# LEDDriverBoardV1_2.net
KiCad netlist of a schematic drawn in EAGLE
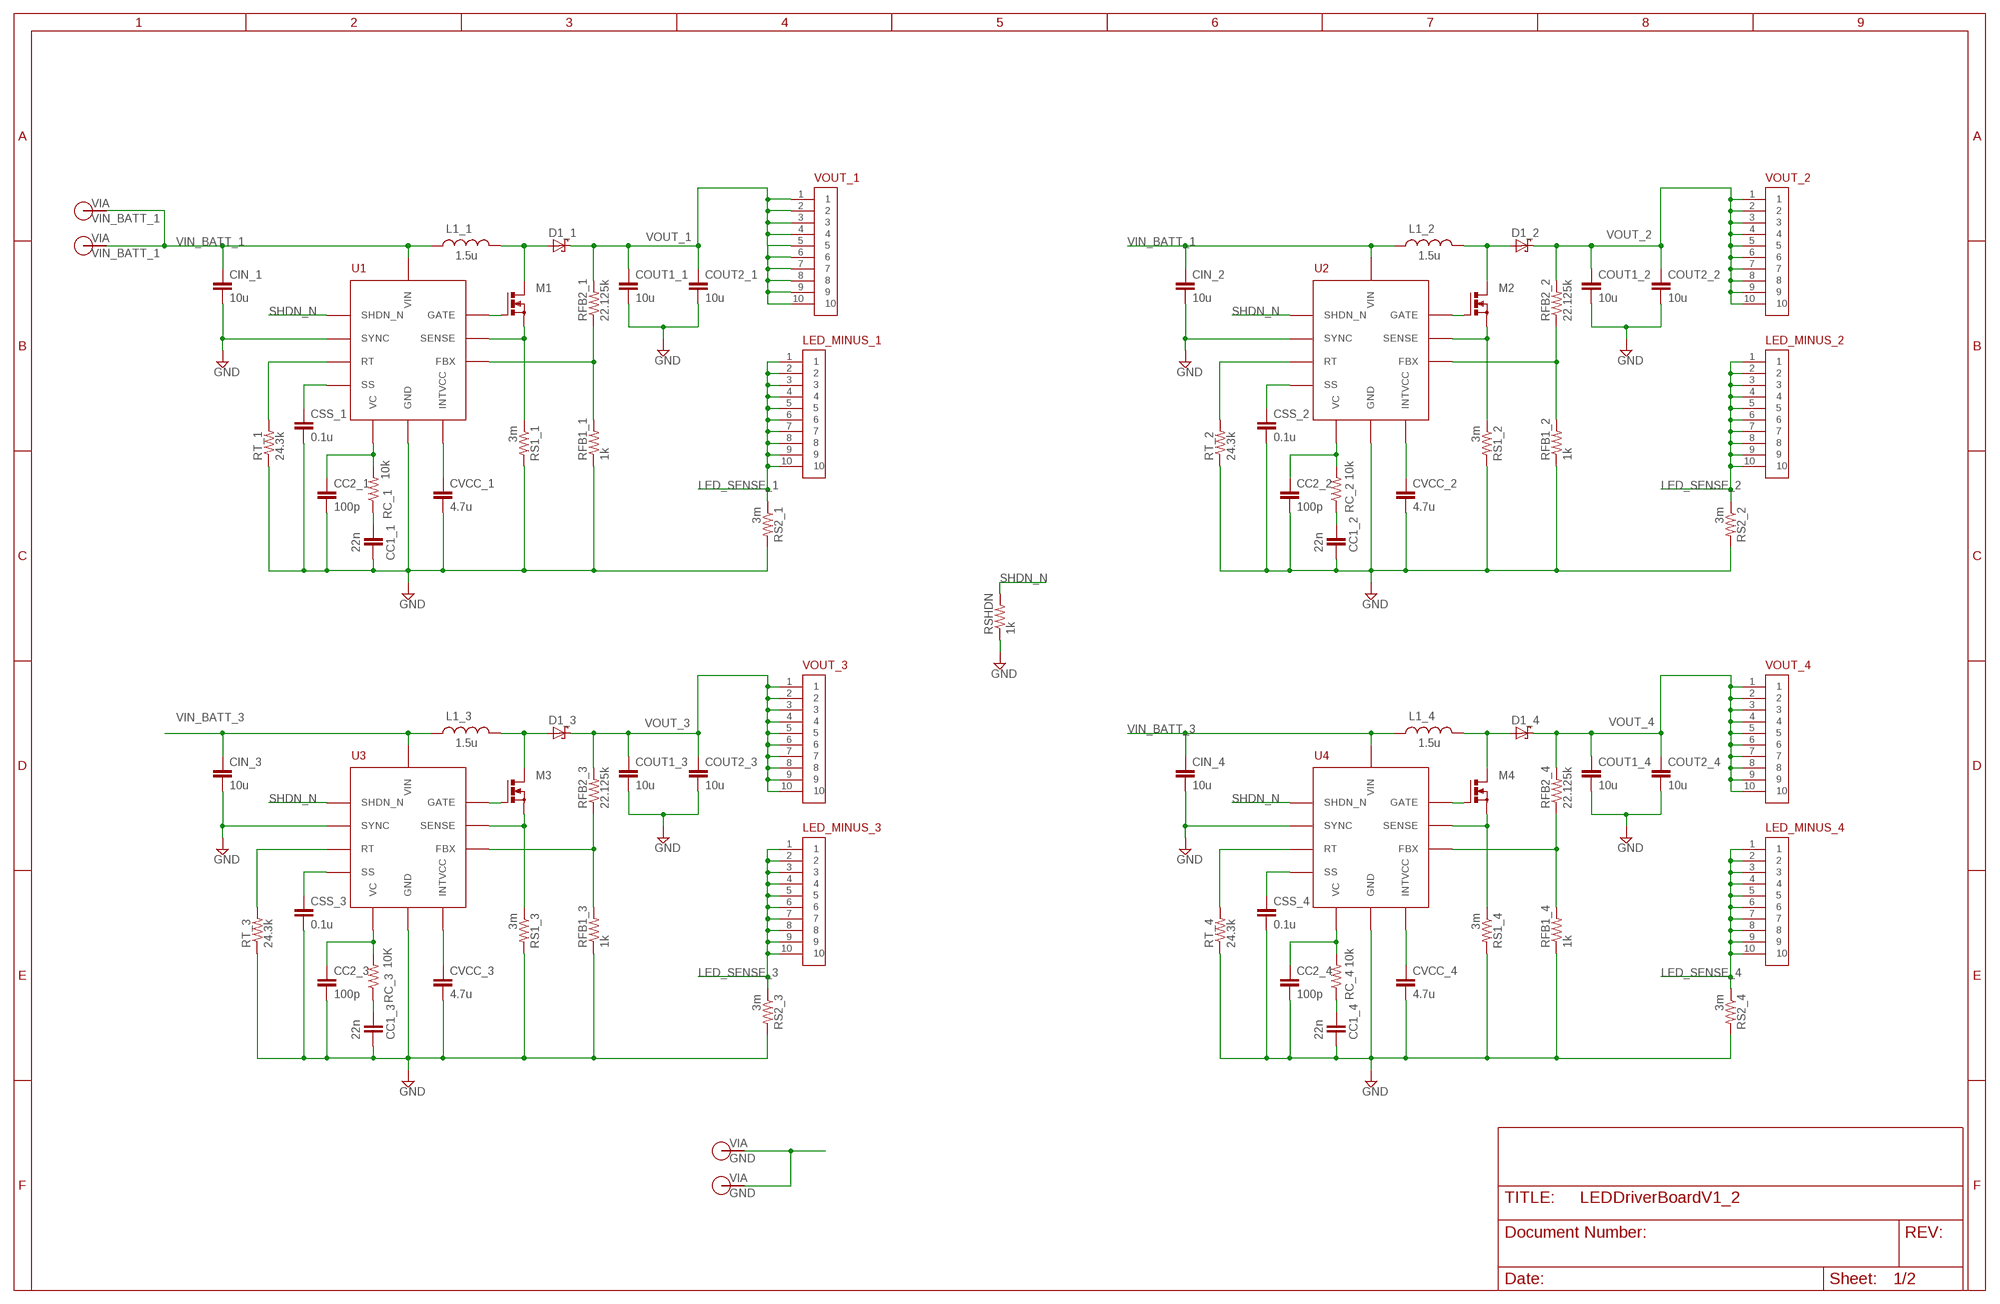
[diagram p0: schematic, sheet 1]
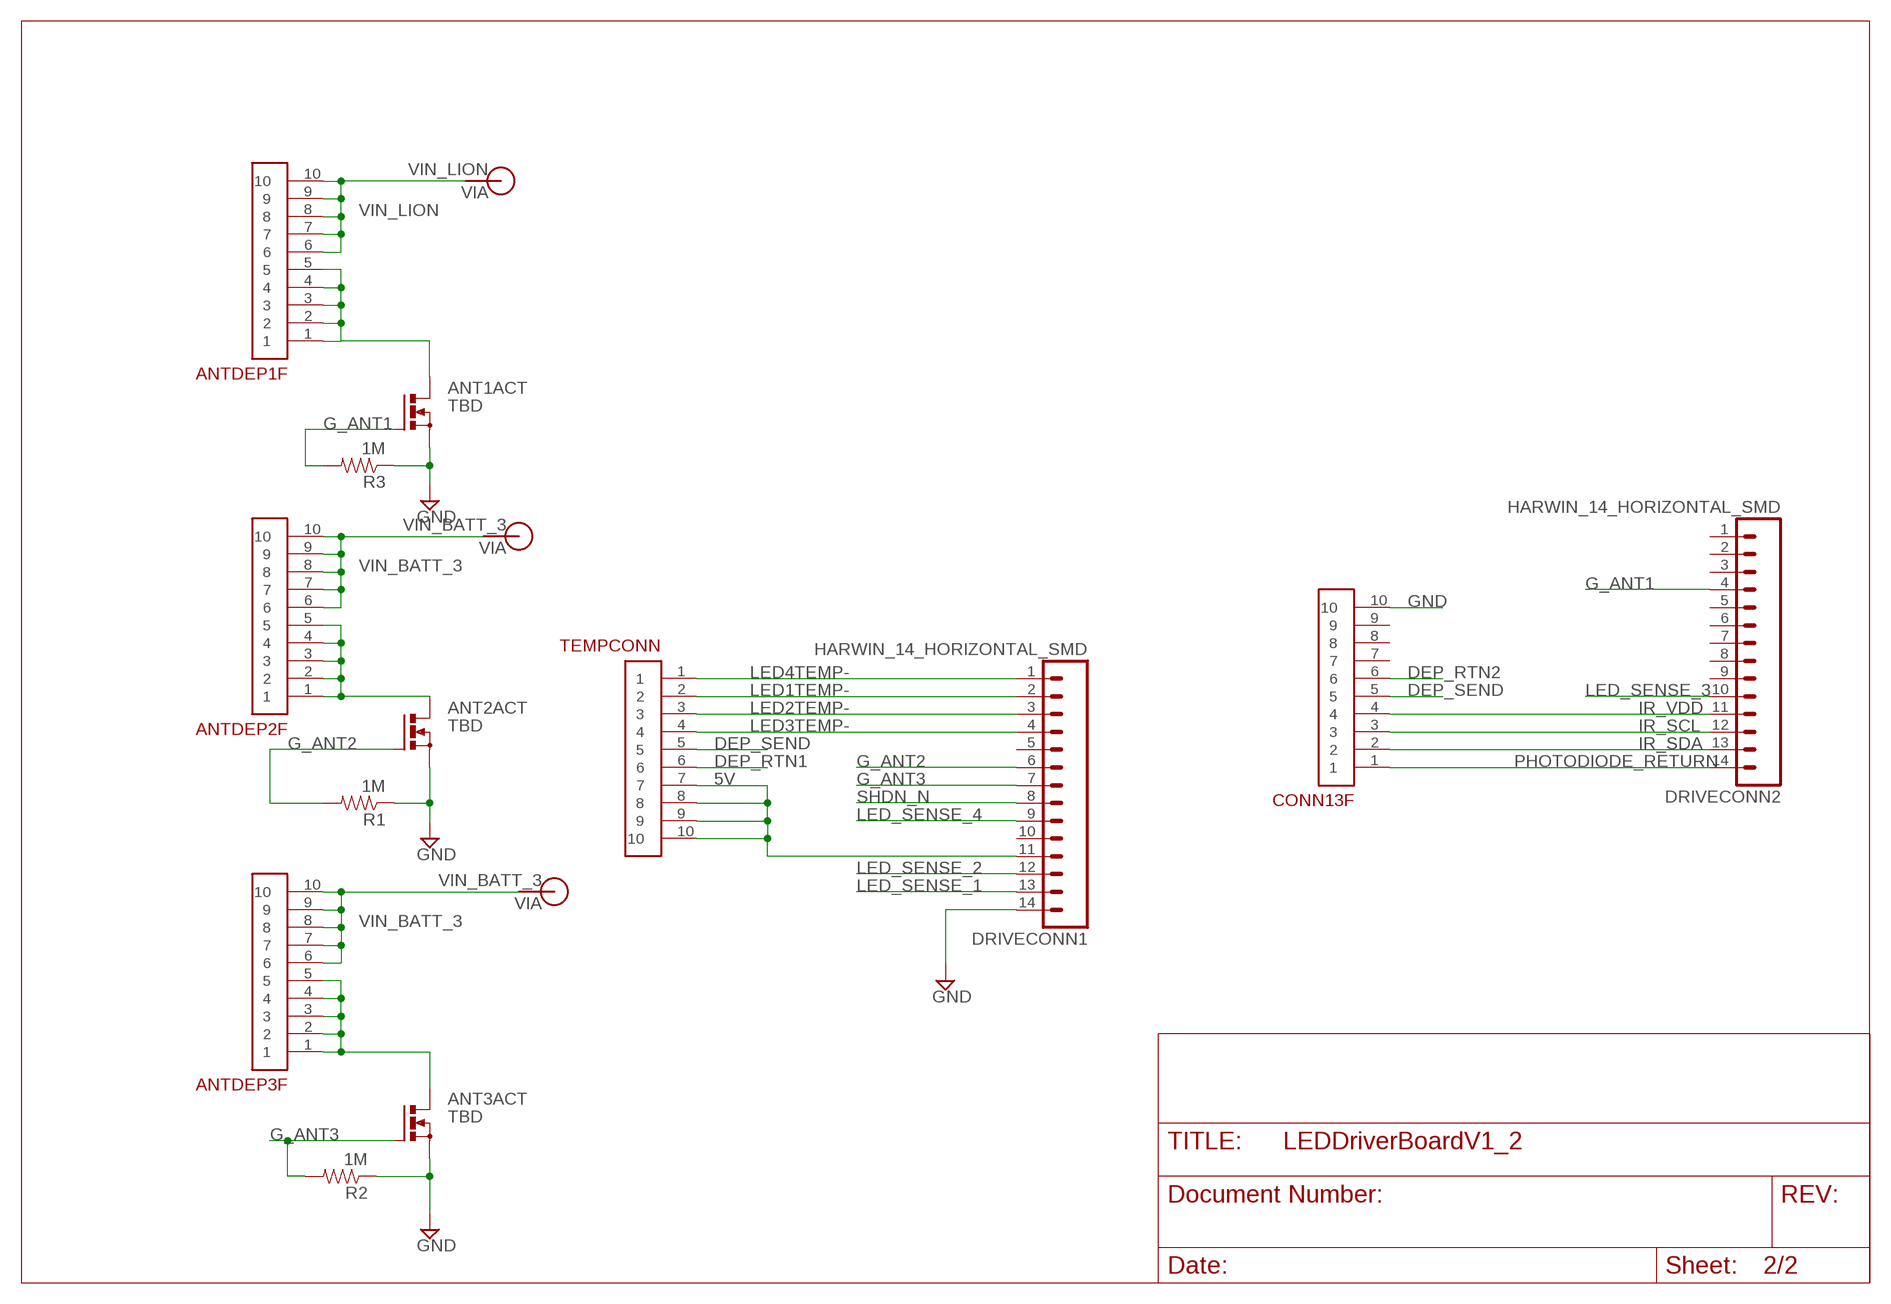
[diagram p1: schematic, sheet 2]

(export (version "E")
  (design (tool "Eeschema 10.0.6"))
  (components
    (comp (ref "CC1_1")
      (value "22n")
      (footprint "eagle-import:C0603")
      (libsource (lib "eagle-import") (part "C-EUC0603"))
    )
    (comp (ref "CC1_2")
      (value "22n")
      (footprint "eagle-import:C0603")
      (libsource (lib "eagle-import") (part "C-EUC0603"))
    )
    (comp (ref "CC1_3")
      (value "22n")
      (footprint "eagle-import:C0603")
      (libsource (lib "eagle-import") (part "C-EUC0603"))
    )
    (comp (ref "CC1_4")
      (value "22n")
      (footprint "eagle-import:C0603")
      (libsource (lib "eagle-import") (part "C-EUC0603"))
    )
    (comp (ref "CC2_1")
      (value "100p")
      (footprint "eagle-import:C0603")
      (libsource (lib "eagle-import") (part "C-EUC0603"))
    )
    (comp (ref "CC2_2")
      (value "100p")
      (footprint "eagle-import:C0603")
      (libsource (lib "eagle-import") (part "C-EUC0603"))
    )
    (comp (ref "CC2_3")
      (value "100p")
      (footprint "eagle-import:C0603")
      (libsource (lib "eagle-import") (part "C-EUC0603"))
    )
    (comp (ref "CC2_4")
      (value "100p")
      (footprint "eagle-import:C0603")
      (libsource (lib "eagle-import") (part "C-EUC0603"))
    )
    (comp (ref "CIN_1")
      (value "10u")
      (footprint "eagle-import:C1210")
      (libsource (lib "eagle-import") (part "C-EUC1210"))
    )
    (comp (ref "CIN_2")
      (value "10u")
      (footprint "eagle-import:C1210")
      (libsource (lib "eagle-import") (part "C-EUC1210"))
    )
    (comp (ref "CIN_3")
      (value "10u")
      (footprint "eagle-import:C1210")
      (libsource (lib "eagle-import") (part "C-EUC1210"))
    )
    (comp (ref "CIN_4")
      (value "10u")
      (footprint "eagle-import:C1210")
      (libsource (lib "eagle-import") (part "C-EUC1210"))
    )
    (comp (ref "COUT1_1")
      (value "10u")
      (footprint "eagle-import:C1210")
      (libsource (lib "eagle-import") (part "C-EUC1210"))
    )
    (comp (ref "COUT1_2")
      (value "10u")
      (footprint "eagle-import:C1210")
      (libsource (lib "eagle-import") (part "C-EUC1210"))
    )
    (comp (ref "COUT1_3")
      (value "10u")
      (footprint "eagle-import:C1210")
      (libsource (lib "eagle-import") (part "C-EUC1210"))
    )
    (comp (ref "COUT1_4")
      (value "10u")
      (footprint "eagle-import:C1210")
      (libsource (lib "eagle-import") (part "C-EUC1210"))
    )
    (comp (ref "COUT2_1")
      (value "10u")
      (footprint "eagle-import:C1210")
      (libsource (lib "eagle-import") (part "C-EUC1210"))
    )
    (comp (ref "COUT2_2")
      (value "10u")
      (footprint "eagle-import:C1210")
      (libsource (lib "eagle-import") (part "C-EUC1210"))
    )
    (comp (ref "COUT2_3")
      (value "10u")
      (footprint "eagle-import:C1210")
      (libsource (lib "eagle-import") (part "C-EUC1210"))
    )
    (comp (ref "COUT2_4")
      (value "10u")
      (footprint "eagle-import:C1210")
      (libsource (lib "eagle-import") (part "C-EUC1210"))
    )
    (comp (ref "CSS_1")
      (value "0.1u")
      (footprint "eagle-import:C0603")
      (libsource (lib "eagle-import") (part "C-EUC0603"))
    )
    (comp (ref "CSS_2")
      (value "0.1u")
      (footprint "eagle-import:C0603")
      (libsource (lib "eagle-import") (part "C-EUC0603"))
    )
    (comp (ref "CSS_3")
      (value "0.1u")
      (footprint "eagle-import:C0603")
      (libsource (lib "eagle-import") (part "C-EUC0603"))
    )
    (comp (ref "CSS_4")
      (value "0.1u")
      (footprint "eagle-import:C0603")
      (libsource (lib "eagle-import") (part "C-EUC0603"))
    )
    (comp (ref "CVCC_1")
      (value "4.7u")
      (footprint "eagle-import:C0603")
      (libsource (lib "eagle-import") (part "C-EUC0603"))
    )
    (comp (ref "CVCC_2")
      (value "4.7u")
      (footprint "eagle-import:C0603")
      (libsource (lib "eagle-import") (part "C-EUC0603"))
    )
    (comp (ref "CVCC_3")
      (value "4.7u")
      (footprint "eagle-import:C0603")
      (libsource (lib "eagle-import") (part "C-EUC0603"))
    )
    (comp (ref "CVCC_4")
      (value "4.7u")
      (footprint "eagle-import:C0603")
      (libsource (lib "eagle-import") (part "C-EUC0603"))
    )
    (comp (ref "D1_1")
      (value "CDBZ5T30100-HF")
      (footprint "eagle-import:SMC(Z5-T)")
      (libsource (lib "eagle-import") (part "CDBZ5T30100-HF"))
    )
    (comp (ref "D1_2")
      (value "CDBZ5T30100-HF")
      (footprint "eagle-import:SMC(Z5-T)")
      (libsource (lib "eagle-import") (part "CDBZ5T30100-HF"))
    )
    (comp (ref "D1_3")
      (value "CDBZ5T30100-HF")
      (footprint "eagle-import:SMC(Z5-T)")
      (libsource (lib "eagle-import") (part "CDBZ5T30100-HF"))
    )
    (comp (ref "D1_4")
      (value "CDBZ5T30100-HF")
      (footprint "eagle-import:SMC(Z5-T)")
      (libsource (lib "eagle-import") (part "CDBZ5T30100-HF"))
    )
    (comp (ref "L1_1")
      (value "1.5u")
      (footprint "eagle-import:SRP1245A")
      (libsource (lib "eagle-import") (part "SRP1245A-1R5M"))
    )
    (comp (ref "L1_2")
      (value "1.5u")
      (footprint "eagle-import:SRP1245A")
      (libsource (lib "eagle-import") (part "SRP1245A-1R5M"))
    )
    (comp (ref "L1_3")
      (value "1.5u")
      (footprint "eagle-import:SRP1245A")
      (libsource (lib "eagle-import") (part "SRP1245A-1R5M"))
    )
    (comp (ref "L1_4")
      (value "1.5u")
      (footprint "eagle-import:SRP1245A")
      (libsource (lib "eagle-import") (part "SRP1245A-1R5M"))
    )
    (comp (ref "LED_MINUS_1")
      (value "M50-3120545")
      (footprint "eagle-import:10PINFEMALE")
      (libsource (lib "eagle-import") (part "M50-3120545"))
    )
    (comp (ref "LED_MINUS_2")
      (value "M50-3120545")
      (footprint "eagle-import:10PINFEMALE")
      (libsource (lib "eagle-import") (part "M50-3120545"))
    )
    (comp (ref "LED_MINUS_3")
      (value "M50-3120545")
      (footprint "eagle-import:10PINFEMALE")
      (libsource (lib "eagle-import") (part "M50-3120545"))
    )
    (comp (ref "LED_MINUS_4")
      (value "M50-3120545")
      (footprint "eagle-import:10PINFEMALE")
      (libsource (lib "eagle-import") (part "M50-3120545"))
    )
    (comp (ref "M1")
      (value "STL110N10F7")
      (footprint "eagle-import:POWERFLAT")
      (libsource (lib "eagle-import") (part "STL110N10F7"))
    )
    (comp (ref "M2")
      (value "STL110N10F7")
      (footprint "eagle-import:POWERFLAT")
      (libsource (lib "eagle-import") (part "STL110N10F7"))
    )
    (comp (ref "M3")
      (value "STL110N10F7")
      (footprint "eagle-import:POWERFLAT")
      (libsource (lib "eagle-import") (part "STL110N10F7"))
    )
    (comp (ref "M4")
      (value "STL110N10F7")
      (footprint "eagle-import:POWERFLAT")
      (libsource (lib "eagle-import") (part "STL110N10F7"))
    )
    (comp (ref "RC_1")
      (value "10k")
      (footprint "eagle-import:R0603")
      (libsource (lib "eagle-import") (part "R-US_R0603"))
    )
    (comp (ref "RC_2")
      (value "10k")
      (footprint "eagle-import:R0603")
      (libsource (lib "eagle-import") (part "R-US_R0603"))
    )
    (comp (ref "RC_3")
      (value "10K")
      (footprint "eagle-import:R0603")
      (libsource (lib "eagle-import") (part "R-US_R0603"))
    )
    (comp (ref "RC_4")
      (value "10k")
      (footprint "eagle-import:R0603")
      (libsource (lib "eagle-import") (part "R-US_R0603"))
    )
    (comp (ref "RFB1_1")
      (value "1k")
      (footprint "eagle-import:R0603")
      (libsource (lib "eagle-import") (part "R-US_R0603"))
    )
    (comp (ref "RFB1_2")
      (value "1k")
      (footprint "eagle-import:R0603")
      (libsource (lib "eagle-import") (part "R-US_R0603"))
    )
    (comp (ref "RFB1_3")
      (value "1k")
      (footprint "eagle-import:R0603")
      (libsource (lib "eagle-import") (part "R-US_R0603"))
    )
    (comp (ref "RFB1_4")
      (value "1k")
      (footprint "eagle-import:R0603")
      (libsource (lib "eagle-import") (part "R-US_R0603"))
    )
    (comp (ref "RFB2_1")
      (value "22.125k")
      (footprint "eagle-import:R0603")
      (libsource (lib "eagle-import") (part "R-US_R0603"))
    )
    (comp (ref "RFB2_2")
      (value "22.125k")
      (footprint "eagle-import:R0603")
      (libsource (lib "eagle-import") (part "R-US_R0603"))
    )
    (comp (ref "RFB2_3")
      (value "22.125k")
      (footprint "eagle-import:R0603")
      (libsource (lib "eagle-import") (part "R-US_R0603"))
    )
    (comp (ref "RFB2_4")
      (value "22.125k")
      (footprint "eagle-import:R0603")
      (libsource (lib "eagle-import") (part "R-US_R0603"))
    )
    (comp (ref "RS1_1")
      (value "3m")
      (footprint "eagle-import:ERJMS4S")
      (libsource (lib "eagle-import") (part "ERJMS4S"))
    )
    (comp (ref "RS1_2")
      (value "3m")
      (footprint "eagle-import:ERJMS4S")
      (libsource (lib "eagle-import") (part "ERJMS4S"))
    )
    (comp (ref "RS1_3")
      (value "3m")
      (footprint "eagle-import:ERJMS4S")
      (libsource (lib "eagle-import") (part "ERJMS4S"))
    )
    (comp (ref "RS1_4")
      (value "3m")
      (footprint "eagle-import:ERJMS4S")
      (libsource (lib "eagle-import") (part "ERJMS4S"))
    )
    (comp (ref "RS2_1")
      (value "3m")
      (footprint "eagle-import:ERJMS4S")
      (libsource (lib "eagle-import") (part "ERJMS4S"))
    )
    (comp (ref "RS2_2")
      (value "3m")
      (footprint "eagle-import:ERJMS4S")
      (libsource (lib "eagle-import") (part "ERJMS4S"))
    )
    (comp (ref "RS2_3")
      (value "3m")
      (footprint "eagle-import:ERJMS4S")
      (libsource (lib "eagle-import") (part "ERJMS4S"))
    )
    (comp (ref "RS2_4")
      (value "3m")
      (footprint "eagle-import:ERJMS4S")
      (libsource (lib "eagle-import") (part "ERJMS4S"))
    )
    (comp (ref "RSHDN")
      (value "1k")
      (footprint "eagle-import:R0603")
      (libsource (lib "eagle-import") (part "R-US_R0603"))
    )
    (comp (ref "RT_1")
      (value "24.3k")
      (footprint "eagle-import:R0603")
      (libsource (lib "eagle-import") (part "R-US_R0603"))
    )
    (comp (ref "RT_2")
      (value "24.3k")
      (footprint "eagle-import:R0603")
      (libsource (lib "eagle-import") (part "R-US_R0603"))
    )
    (comp (ref "RT_3")
      (value "24.3k")
      (footprint "eagle-import:R0603")
      (libsource (lib "eagle-import") (part "R-US_R0603"))
    )
    (comp (ref "RT_4")
      (value "24.3k")
      (footprint "eagle-import:R0603")
      (libsource (lib "eagle-import") (part "R-US_R0603"))
    )
    (comp (ref "U1")
      (value "LT3757")
      (footprint "eagle-import:MSOP10")
      (libsource (lib "eagle-import") (part "LT3757"))
    )
    (comp (ref "U2")
      (value "LT3757")
      (footprint "eagle-import:MSOP10")
      (libsource (lib "eagle-import") (part "LT3757"))
    )
    (comp (ref "U3")
      (value "LT3757")
      (footprint "eagle-import:MSOP10")
      (libsource (lib "eagle-import") (part "LT3757"))
    )
    (comp (ref "U4")
      (value "LT3757")
      (footprint "eagle-import:MSOP10")
      (libsource (lib "eagle-import") (part "LT3757"))
    )
    (comp (ref "V1")
      (value "GND")
      (footprint "eagle-import:VIA-120MIL")
      (libsource (lib "eagle-import") (part "VIA-120MIL"))
    )
    (comp (ref "V5")
      (value "GND")
      (footprint "eagle-import:VIA-120MIL")
      (libsource (lib "eagle-import") (part "VIA-120MIL"))
    )
    (comp (ref "V6")
      (value "VIN_BATT_1")
      (footprint "eagle-import:VIA-120MIL")
      (libsource (lib "eagle-import") (part "VIA-120MIL"))
    )
    (comp (ref "V7")
      (value "VIN_BATT_1")
      (footprint "eagle-import:VIA-120MIL")
      (libsource (lib "eagle-import") (part "VIA-120MIL"))
    )
    (comp (ref "VOUT_1")
      (value "M50-3120545")
      (footprint "eagle-import:10PINFEMALE")
      (libsource (lib "eagle-import") (part "M50-3120545"))
    )
    (comp (ref "VOUT_2")
      (value "M50-3120545")
      (footprint "eagle-import:10PINFEMALE")
      (libsource (lib "eagle-import") (part "M50-3120545"))
    )
    (comp (ref "VOUT_3")
      (value "M50-3120545")
      (footprint "eagle-import:10PINFEMALE")
      (libsource (lib "eagle-import") (part "M50-3120545"))
    )
    (comp (ref "VOUT_4")
      (value "M50-3120545")
      (footprint "eagle-import:10PINFEMALE")
      (libsource (lib "eagle-import") (part "M50-3120545"))
    )
    (comp (ref "ANT1ACT")
      (value "TBD")
      (footprint "eagle-import:DFN3.3X3.3")
      (libsource (lib "eagle-import") (part "AON7292"))
    )
    (comp (ref "ANT2ACT")
      (value "TBD")
      (footprint "eagle-import:DFN3.3X3.3")
      (libsource (lib "eagle-import") (part "AON7292"))
    )
    (comp (ref "ANT3ACT")
      (value "TBD")
      (footprint "eagle-import:DFN3.3X3.3")
      (libsource (lib "eagle-import") (part "AON7292"))
    )
    (comp (ref "ANTDEP1F")
      (value "M50-3120545")
      (footprint "eagle-import:10PINFEMALE")
      (libsource (lib "eagle-import") (part "M50-3120545"))
    )
    (comp (ref "ANTDEP2F")
      (value "M50-3120545")
      (footprint "eagle-import:10PINFEMALE")
      (libsource (lib "eagle-import") (part "M50-3120545"))
    )
    (comp (ref "ANTDEP3F")
      (value "M50-3120545")
      (footprint "eagle-import:10PINFEMALE")
      (libsource (lib "eagle-import") (part "M50-3120545"))
    )
    (comp (ref "CONN13F")
      (value "M50-3120545")
      (footprint "eagle-import:10PINFEMALE")
      (libsource (lib "eagle-import") (part "M50-3120545"))
    )
    (comp (ref "DRIVECONN1")
      (value "HARWIN_14_HORIZONTAL_SMD")
      (footprint "eagle-import:14PINMALE_SMD")
      (libsource (lib "eagle-import") (part "M80-5321442"))
    )
    (comp (ref "DRIVECONN2")
      (value "HARWIN_14_HORIZONTAL_SMD")
      (footprint "eagle-import:14PINMALE_SMD")
      (libsource (lib "eagle-import") (part "M80-5321442"))
    )
    (comp (ref "R1")
      (value "1M")
      (footprint "eagle-import:0805")
      (libsource (lib "eagle-import") (part "RESISTOR"))
    )
    (comp (ref "R2")
      (value "1M")
      (footprint "eagle-import:0805")
      (libsource (lib "eagle-import") (part "RESISTOR"))
    )
    (comp (ref "R3")
      (value "1M")
      (footprint "eagle-import:0805")
      (libsource (lib "eagle-import") (part "RESISTOR"))
    )
    (comp (ref "TEMPCONN")
      (value "M50-3120545")
      (footprint "eagle-import:10PINFEMALE")
      (libsource (lib "eagle-import") (part "M50-3120545"))
    )
    (comp (ref "V2")
      (value "VIN_BATT_3")
      (footprint "eagle-import:VIA-120MIL")
      (libsource (lib "eagle-import") (part "VIA-120MIL"))
    )
    (comp (ref "V3")
      (value "VIN_BATT_3")
      (footprint "eagle-import:VIA-120MIL")
      (libsource (lib "eagle-import") (part "VIA-120MIL"))
    )
    (comp (ref "V4")
      (value "VIN_LION")
      (footprint "eagle-import:VIA-120MIL")
      (libsource (lib "eagle-import") (part "VIA-120MIL"))
    )
  )
  (nets
    (net (code "1") (name "5V") (class "Default")
      (node (ref "DRIVECONN1") (pin "11") (pinfunction "11_11") (pintype "passive"))
      (node (ref "TEMPCONN") (pin "10") (pinfunction "10_10") (pintype "bidirectional"))
      (node (ref "TEMPCONN") (pin "7") (pinfunction "7_7") (pintype "bidirectional"))
      (node (ref "TEMPCONN") (pin "8") (pinfunction "8_8") (pintype "bidirectional"))
      (node (ref "TEMPCONN") (pin "9") (pinfunction "9_9") (pintype "bidirectional"))
    )
    (net (code "2") (name "DEP_RTN1") (class "Default")
      (node (ref "TEMPCONN") (pin "6") (pinfunction "6_6") (pintype "bidirectional"))
    )
    (net (code "3") (name "DEP_RTN2") (class "Default")
      (node (ref "CONN13F") (pin "6") (pinfunction "6_6") (pintype "bidirectional"))
    )
    (net (code "4") (name "DEP_SEND") (class "Default")
      (node (ref "CONN13F") (pin "5") (pinfunction "5_5") (pintype "bidirectional"))
      (node (ref "TEMPCONN") (pin "5") (pinfunction "5_5") (pintype "bidirectional"))
    )
    (net (code "5") (name "GND") (class "Default")
      (node (ref "ANT1ACT") (pin "S1") (pinfunction "S_S1") (pintype "passive"))
      (node (ref "ANT1ACT") (pin "S2") (pinfunction "S_S2") (pintype "passive"))
      (node (ref "ANT1ACT") (pin "S3") (pinfunction "S_S3") (pintype "passive"))
      (node (ref "ANT2ACT") (pin "S1") (pinfunction "S_S1") (pintype "passive"))
      (node (ref "ANT2ACT") (pin "S2") (pinfunction "S_S2") (pintype "passive"))
      (node (ref "ANT2ACT") (pin "S3") (pinfunction "S_S3") (pintype "passive"))
      (node (ref "ANT3ACT") (pin "S1") (pinfunction "S_S1") (pintype "passive"))
      (node (ref "ANT3ACT") (pin "S2") (pinfunction "S_S2") (pintype "passive"))
      (node (ref "ANT3ACT") (pin "S3") (pinfunction "S_S3") (pintype "passive"))
      (node (ref "CC1_1") (pin "2") (pinfunction "2_2") (pintype "passive"))
      (node (ref "CC1_2") (pin "2") (pinfunction "2_2") (pintype "passive"))
      (node (ref "CC1_3") (pin "2") (pinfunction "2_2") (pintype "passive"))
      (node (ref "CC1_4") (pin "2") (pinfunction "2_2") (pintype "passive"))
      (node (ref "CC2_1") (pin "2") (pinfunction "2_2") (pintype "passive"))
      (node (ref "CC2_2") (pin "2") (pinfunction "2_2") (pintype "passive"))
      (node (ref "CC2_3") (pin "2") (pinfunction "2_2") (pintype "passive"))
      (node (ref "CC2_4") (pin "2") (pinfunction "2_2") (pintype "passive"))
      (node (ref "CIN_1") (pin "2") (pinfunction "2_2") (pintype "passive"))
      (node (ref "CIN_2") (pin "2") (pinfunction "2_2") (pintype "passive"))
      (node (ref "CIN_3") (pin "2") (pinfunction "2_2") (pintype "passive"))
      (node (ref "CIN_4") (pin "2") (pinfunction "2_2") (pintype "passive"))
      (node (ref "CONN13F") (pin "10") (pinfunction "10_10") (pintype "bidirectional"))
      (node (ref "COUT1_1") (pin "2") (pinfunction "2_2") (pintype "passive"))
      (node (ref "COUT1_2") (pin "2") (pinfunction "2_2") (pintype "passive"))
      (node (ref "COUT1_3") (pin "2") (pinfunction "2_2") (pintype "passive"))
      (node (ref "COUT1_4") (pin "2") (pinfunction "2_2") (pintype "passive"))
      (node (ref "COUT2_1") (pin "2") (pinfunction "2_2") (pintype "passive"))
      (node (ref "COUT2_2") (pin "2") (pinfunction "2_2") (pintype "passive"))
      (node (ref "COUT2_3") (pin "2") (pinfunction "2_2") (pintype "passive"))
      (node (ref "COUT2_4") (pin "2") (pinfunction "2_2") (pintype "passive"))
      (node (ref "CSS_1") (pin "2") (pinfunction "2_2") (pintype "passive"))
      (node (ref "CSS_2") (pin "2") (pinfunction "2_2") (pintype "passive"))
      (node (ref "CSS_3") (pin "2") (pinfunction "2_2") (pintype "passive"))
      (node (ref "CSS_4") (pin "2") (pinfunction "2_2") (pintype "passive"))
      (node (ref "CVCC_1") (pin "2") (pinfunction "2_2") (pintype "passive"))
      (node (ref "CVCC_2") (pin "2") (pinfunction "2_2") (pintype "passive"))
      (node (ref "CVCC_3") (pin "2") (pinfunction "2_2") (pintype "passive"))
      (node (ref "CVCC_4") (pin "2") (pinfunction "2_2") (pintype "passive"))
      (node (ref "DRIVECONN1") (pin "14") (pinfunction "14_14") (pintype "passive"))
      (node (ref "R1") (pin "1") (pinfunction "1_1") (pintype "passive"))
      (node (ref "R2") (pin "1") (pinfunction "1_1") (pintype "passive"))
      (node (ref "R3") (pin "1") (pinfunction "1_1") (pintype "passive"))
      (node (ref "RFB1_1") (pin "1") (pinfunction "1_1") (pintype "passive"))
      (node (ref "RFB1_2") (pin "1") (pinfunction "1_1") (pintype "passive"))
      (node (ref "RFB1_3") (pin "1") (pinfunction "1_1") (pintype "passive"))
      (node (ref "RFB1_4") (pin "1") (pinfunction "1_1") (pintype "passive"))
      (node (ref "RS1_1") (pin "B") (pinfunction "2_B") (pintype "passive"))
      (node (ref "RS1_2") (pin "B") (pinfunction "2_B") (pintype "passive"))
      (node (ref "RS1_3") (pin "B") (pinfunction "2_B") (pintype "passive"))
      (node (ref "RS1_4") (pin "B") (pinfunction "2_B") (pintype "passive"))
      (node (ref "RS2_1") (pin "B") (pinfunction "2_B") (pintype "passive"))
      (node (ref "RS2_2") (pin "B") (pinfunction "2_B") (pintype "passive"))
      (node (ref "RS2_3") (pin "B") (pinfunction "2_B") (pintype "passive"))
      (node (ref "RS2_4") (pin "B") (pinfunction "2_B") (pintype "passive"))
      (node (ref "RSHDN") (pin "1") (pinfunction "1_1") (pintype "passive"))
      (node (ref "RT_1") (pin "1") (pinfunction "1_1") (pintype "passive"))
      (node (ref "RT_2") (pin "1") (pinfunction "1_1") (pintype "passive"))
      (node (ref "RT_3") (pin "1") (pinfunction "1_1") (pintype "passive"))
      (node (ref "RT_4") (pin "1") (pinfunction "1_1") (pintype "passive"))
      (node (ref "U1") (pin "P$11") (pinfunction "GND_P$11") (pintype "bidirectional"))
      (node (ref "U1") (pin "P$5") (pinfunction "SYNC_P$5") (pintype "bidirectional"))
      (node (ref "U2") (pin "P$11") (pinfunction "GND_P$11") (pintype "bidirectional"))
      (node (ref "U2") (pin "P$5") (pinfunction "SYNC_P$5") (pintype "bidirectional"))
      (node (ref "U3") (pin "P$11") (pinfunction "GND_P$11") (pintype "bidirectional"))
      (node (ref "U3") (pin "P$5") (pinfunction "SYNC_P$5") (pintype "bidirectional"))
      (node (ref "U4") (pin "P$11") (pinfunction "GND_P$11") (pintype "bidirectional"))
      (node (ref "U4") (pin "P$5") (pinfunction "SYNC_P$5") (pintype "bidirectional"))
      (node (ref "V1") (pin "P$1") (pinfunction "P$1_P$1") (pintype "bidirectional"))
      (node (ref "V5") (pin "P$1") (pinfunction "P$1_P$1") (pintype "bidirectional"))
    )
    (net (code "6") (name "G_ANT1") (class "Default")
      (node (ref "ANT1ACT") (pin "G") (pinfunction "G_G") (pintype "passive"))
      (node (ref "DRIVECONN2") (pin "4") (pinfunction "4_4") (pintype "passive"))
      (node (ref "R3") (pin "2") (pinfunction "2_2") (pintype "passive"))
    )
    (net (code "7") (name "G_ANT2") (class "Default")
      (node (ref "ANT2ACT") (pin "G") (pinfunction "G_G") (pintype "passive"))
      (node (ref "DRIVECONN1") (pin "6") (pinfunction "6_6") (pintype "passive"))
      (node (ref "R1") (pin "2") (pinfunction "2_2") (pintype "passive"))
    )
    (net (code "8") (name "G_ANT3") (class "Default")
      (node (ref "ANT3ACT") (pin "G") (pinfunction "G_G") (pintype "passive"))
      (node (ref "DRIVECONN1") (pin "7") (pinfunction "7_7") (pintype "passive"))
      (node (ref "R2") (pin "2") (pinfunction "2_2") (pintype "passive"))
    )
    (net (code "9") (name "IR_SCL") (class "Default")
      (node (ref "CONN13F") (pin "3") (pinfunction "3_3") (pintype "bidirectional"))
      (node (ref "DRIVECONN2") (pin "12") (pinfunction "12_12") (pintype "passive"))
    )
    (net (code "10") (name "IR_SDA") (class "Default")
      (node (ref "CONN13F") (pin "2") (pinfunction "2_2") (pintype "bidirectional"))
      (node (ref "DRIVECONN2") (pin "13") (pinfunction "13_13") (pintype "passive"))
    )
    (net (code "11") (name "IR_VDD") (class "Default")
      (node (ref "CONN13F") (pin "4") (pinfunction "4_4") (pintype "bidirectional"))
      (node (ref "DRIVECONN2") (pin "11") (pinfunction "11_11") (pintype "passive"))
    )
    (net (code "12") (name "LED1TEMP-") (class "Default")
      (node (ref "DRIVECONN1") (pin "2") (pinfunction "2_2") (pintype "passive"))
      (node (ref "TEMPCONN") (pin "2") (pinfunction "2_2") (pintype "bidirectional"))
    )
    (net (code "13") (name "LED2TEMP-") (class "Default")
      (node (ref "DRIVECONN1") (pin "3") (pinfunction "3_3") (pintype "passive"))
      (node (ref "TEMPCONN") (pin "3") (pinfunction "3_3") (pintype "bidirectional"))
    )
    (net (code "14") (name "LED3TEMP-") (class "Default")
      (node (ref "DRIVECONN1") (pin "4") (pinfunction "4_4") (pintype "passive"))
      (node (ref "TEMPCONN") (pin "4") (pinfunction "4_4") (pintype "bidirectional"))
    )
    (net (code "15") (name "LED4TEMP-") (class "Default")
      (node (ref "DRIVECONN1") (pin "1") (pinfunction "1_1") (pintype "passive"))
      (node (ref "TEMPCONN") (pin "1") (pinfunction "1_1") (pintype "bidirectional"))
    )
    (net (code "16") (name "LED_SENSE_1") (class "Default")
      (node (ref "DRIVECONN1") (pin "13") (pinfunction "13_13") (pintype "passive"))
      (node (ref "LED_MINUS_1") (pin "1") (pinfunction "1_1") (pintype "bidirectional"))
      (node (ref "LED_MINUS_1") (pin "10") (pinfunction "10_10") (pintype "bidirectional"))
      (node (ref "LED_MINUS_1") (pin "2") (pinfunction "2_2") (pintype "bidirectional"))
      (node (ref "LED_MINUS_1") (pin "3") (pinfunction "3_3") (pintype "bidirectional"))
      (node (ref "LED_MINUS_1") (pin "4") (pinfunction "4_4") (pintype "bidirectional"))
      (node (ref "LED_MINUS_1") (pin "5") (pinfunction "5_5") (pintype "bidirectional"))
      (node (ref "LED_MINUS_1") (pin "6") (pinfunction "6_6") (pintype "bidirectional"))
      (node (ref "LED_MINUS_1") (pin "7") (pinfunction "7_7") (pintype "bidirectional"))
      (node (ref "LED_MINUS_1") (pin "8") (pinfunction "8_8") (pintype "bidirectional"))
      (node (ref "LED_MINUS_1") (pin "9") (pinfunction "9_9") (pintype "bidirectional"))
      (node (ref "RS2_1") (pin "A") (pinfunction "1_A") (pintype "passive"))
    )
    (net (code "17") (name "LED_SENSE_2") (class "Default")
      (node (ref "DRIVECONN1") (pin "12") (pinfunction "12_12") (pintype "passive"))
      (node (ref "LED_MINUS_2") (pin "1") (pinfunction "1_1") (pintype "bidirectional"))
      (node (ref "LED_MINUS_2") (pin "10") (pinfunction "10_10") (pintype "bidirectional"))
      (node (ref "LED_MINUS_2") (pin "2") (pinfunction "2_2") (pintype "bidirectional"))
      (node (ref "LED_MINUS_2") (pin "3") (pinfunction "3_3") (pintype "bidirectional"))
      (node (ref "LED_MINUS_2") (pin "4") (pinfunction "4_4") (pintype "bidirectional"))
      (node (ref "LED_MINUS_2") (pin "5") (pinfunction "5_5") (pintype "bidirectional"))
      (node (ref "LED_MINUS_2") (pin "6") (pinfunction "6_6") (pintype "bidirectional"))
      (node (ref "LED_MINUS_2") (pin "7") (pinfunction "7_7") (pintype "bidirectional"))
      (node (ref "LED_MINUS_2") (pin "8") (pinfunction "8_8") (pintype "bidirectional"))
      (node (ref "LED_MINUS_2") (pin "9") (pinfunction "9_9") (pintype "bidirectional"))
      (node (ref "RS2_2") (pin "A") (pinfunction "1_A") (pintype "passive"))
    )
    (net (code "18") (name "LED_SENSE_3") (class "Default")
      (node (ref "DRIVECONN2") (pin "10") (pinfunction "10_10") (pintype "passive"))
      (node (ref "LED_MINUS_3") (pin "1") (pinfunction "1_1") (pintype "bidirectional"))
      (node (ref "LED_MINUS_3") (pin "10") (pinfunction "10_10") (pintype "bidirectional"))
      (node (ref "LED_MINUS_3") (pin "2") (pinfunction "2_2") (pintype "bidirectional"))
      (node (ref "LED_MINUS_3") (pin "3") (pinfunction "3_3") (pintype "bidirectional"))
      (node (ref "LED_MINUS_3") (pin "4") (pinfunction "4_4") (pintype "bidirectional"))
      (node (ref "LED_MINUS_3") (pin "5") (pinfunction "5_5") (pintype "bidirectional"))
      (node (ref "LED_MINUS_3") (pin "6") (pinfunction "6_6") (pintype "bidirectional"))
      (node (ref "LED_MINUS_3") (pin "7") (pinfunction "7_7") (pintype "bidirectional"))
      (node (ref "LED_MINUS_3") (pin "8") (pinfunction "8_8") (pintype "bidirectional"))
      (node (ref "LED_MINUS_3") (pin "9") (pinfunction "9_9") (pintype "bidirectional"))
      (node (ref "RS2_3") (pin "A") (pinfunction "1_A") (pintype "passive"))
    )
    (net (code "19") (name "LED_SENSE_4") (class "Default")
      (node (ref "DRIVECONN1") (pin "9") (pinfunction "9_9") (pintype "passive"))
      (node (ref "LED_MINUS_4") (pin "1") (pinfunction "1_1") (pintype "bidirectional"))
      (node (ref "LED_MINUS_4") (pin "10") (pinfunction "10_10") (pintype "bidirectional"))
      (node (ref "LED_MINUS_4") (pin "2") (pinfunction "2_2") (pintype "bidirectional"))
      (node (ref "LED_MINUS_4") (pin "3") (pinfunction "3_3") (pintype "bidirectional"))
      (node (ref "LED_MINUS_4") (pin "4") (pinfunction "4_4") (pintype "bidirectional"))
      (node (ref "LED_MINUS_4") (pin "5") (pinfunction "5_5") (pintype "bidirectional"))
      (node (ref "LED_MINUS_4") (pin "6") (pinfunction "6_6") (pintype "bidirectional"))
      (node (ref "LED_MINUS_4") (pin "7") (pinfunction "7_7") (pintype "bidirectional"))
      (node (ref "LED_MINUS_4") (pin "8") (pinfunction "8_8") (pintype "bidirectional"))
      (node (ref "LED_MINUS_4") (pin "9") (pinfunction "9_9") (pintype "bidirectional"))
      (node (ref "RS2_4") (pin "A") (pinfunction "1_A") (pintype "passive"))
    )
    (net (code "20") (name "Net-(ANT1ACT-D-PadD1)") (class "Default")
      (node (ref "ANT1ACT") (pin "D1") (pinfunction "D_D1") (pintype "passive"))
      (node (ref "ANT1ACT") (pin "D2") (pinfunction "D_D2") (pintype "passive"))
      (node (ref "ANT1ACT") (pin "D3") (pinfunction "D_D3") (pintype "passive"))
      (node (ref "ANT1ACT") (pin "D4") (pinfunction "D_D4") (pintype "passive"))
      (node (ref "ANT1ACT") (pin "D5") (pinfunction "D_D5") (pintype "passive"))
      (node (ref "ANTDEP1F") (pin "1") (pinfunction "1_1") (pintype "bidirectional"))
      (node (ref "ANTDEP1F") (pin "2") (pinfunction "2_2") (pintype "bidirectional"))
      (node (ref "ANTDEP1F") (pin "3") (pinfunction "3_3") (pintype "bidirectional"))
      (node (ref "ANTDEP1F") (pin "4") (pinfunction "4_4") (pintype "bidirectional"))
      (node (ref "ANTDEP1F") (pin "5") (pinfunction "5_5") (pintype "bidirectional"))
    )
    (net (code "21") (name "Net-(ANT2ACT-D-PadD1)") (class "Default")
      (node (ref "ANT2ACT") (pin "D1") (pinfunction "D_D1") (pintype "passive"))
      (node (ref "ANT2ACT") (pin "D2") (pinfunction "D_D2") (pintype "passive"))
      (node (ref "ANT2ACT") (pin "D3") (pinfunction "D_D3") (pintype "passive"))
      (node (ref "ANT2ACT") (pin "D4") (pinfunction "D_D4") (pintype "passive"))
      (node (ref "ANT2ACT") (pin "D5") (pinfunction "D_D5") (pintype "passive"))
      (node (ref "ANTDEP2F") (pin "1") (pinfunction "1_1") (pintype "bidirectional"))
      (node (ref "ANTDEP2F") (pin "2") (pinfunction "2_2") (pintype "bidirectional"))
      (node (ref "ANTDEP2F") (pin "3") (pinfunction "3_3") (pintype "bidirectional"))
      (node (ref "ANTDEP2F") (pin "4") (pinfunction "4_4") (pintype "bidirectional"))
      (node (ref "ANTDEP2F") (pin "5") (pinfunction "5_5") (pintype "bidirectional"))
    )
    (net (code "22") (name "Net-(ANT3ACT-D-PadD1)") (class "Default")
      (node (ref "ANT3ACT") (pin "D1") (pinfunction "D_D1") (pintype "passive"))
      (node (ref "ANT3ACT") (pin "D2") (pinfunction "D_D2") (pintype "passive"))
      (node (ref "ANT3ACT") (pin "D3") (pinfunction "D_D3") (pintype "passive"))
      (node (ref "ANT3ACT") (pin "D4") (pinfunction "D_D4") (pintype "passive"))
      (node (ref "ANT3ACT") (pin "D5") (pinfunction "D_D5") (pintype "passive"))
      (node (ref "ANTDEP3F") (pin "1") (pinfunction "1_1") (pintype "bidirectional"))
      (node (ref "ANTDEP3F") (pin "2") (pinfunction "2_2") (pintype "bidirectional"))
      (node (ref "ANTDEP3F") (pin "3") (pinfunction "3_3") (pintype "bidirectional"))
      (node (ref "ANTDEP3F") (pin "4") (pinfunction "4_4") (pintype "bidirectional"))
      (node (ref "ANTDEP3F") (pin "5") (pinfunction "5_5") (pintype "bidirectional"))
    )
    (net (code "23") (name "Net-(CC1_1-Pad1)") (class "Default")
      (node (ref "CC1_1") (pin "1") (pinfunction "1_1") (pintype "passive"))
      (node (ref "RC_1") (pin "1") (pinfunction "1_1") (pintype "passive"))
    )
    (net (code "24") (name "Net-(CC1_2-Pad1)") (class "Default")
      (node (ref "CC1_2") (pin "1") (pinfunction "1_1") (pintype "passive"))
      (node (ref "RC_2") (pin "1") (pinfunction "1_1") (pintype "passive"))
    )
    (net (code "25") (name "Net-(CC1_3-Pad1)") (class "Default")
      (node (ref "CC1_3") (pin "1") (pinfunction "1_1") (pintype "passive"))
      (node (ref "RC_3") (pin "1") (pinfunction "1_1") (pintype "passive"))
    )
    (net (code "26") (name "Net-(CC1_4-Pad1)") (class "Default")
      (node (ref "CC1_4") (pin "1") (pinfunction "1_1") (pintype "passive"))
      (node (ref "RC_4") (pin "1") (pinfunction "1_1") (pintype "passive"))
    )
    (net (code "27") (name "Net-(L1_1-2)") (class "Default")
      (node (ref "D1_1") (pin "ANODE") (pinfunction "ANODE_ANODE") (pintype "passive"))
      (node (ref "L1_1") (pin "P$2") (pinfunction "2_P$2") (pintype "passive"))
      (node (ref "M1") (pin "D") (pinfunction "D_D") (pintype "passive"))
      (node (ref "M1") (pin "D5") (pinfunction "D_D5") (pintype "passive"))
      (node (ref "M1") (pin "D6") (pinfunction "D_D6") (pintype "passive"))
      (node (ref "M1") (pin "D7") (pinfunction "D_D7") (pintype "passive"))
      (node (ref "M1") (pin "D8") (pinfunction "D_D8") (pintype "passive"))
    )
    (net (code "28") (name "Net-(L1_2-2)") (class "Default")
      (node (ref "D1_2") (pin "ANODE") (pinfunction "ANODE_ANODE") (pintype "passive"))
      (node (ref "L1_2") (pin "P$2") (pinfunction "2_P$2") (pintype "passive"))
      (node (ref "M2") (pin "D") (pinfunction "D_D") (pintype "passive"))
      (node (ref "M2") (pin "D5") (pinfunction "D_D5") (pintype "passive"))
      (node (ref "M2") (pin "D6") (pinfunction "D_D6") (pintype "passive"))
      (node (ref "M2") (pin "D7") (pinfunction "D_D7") (pintype "passive"))
      (node (ref "M2") (pin "D8") (pinfunction "D_D8") (pintype "passive"))
    )
    (net (code "29") (name "Net-(L1_3-2)") (class "Default")
      (node (ref "D1_3") (pin "ANODE") (pinfunction "ANODE_ANODE") (pintype "passive"))
      (node (ref "L1_3") (pin "P$2") (pinfunction "2_P$2") (pintype "passive"))
      (node (ref "M3") (pin "D") (pinfunction "D_D") (pintype "passive"))
      (node (ref "M3") (pin "D5") (pinfunction "D_D5") (pintype "passive"))
      (node (ref "M3") (pin "D6") (pinfunction "D_D6") (pintype "passive"))
      (node (ref "M3") (pin "D7") (pinfunction "D_D7") (pintype "passive"))
      (node (ref "M3") (pin "D8") (pinfunction "D_D8") (pintype "passive"))
    )
    (net (code "30") (name "Net-(L1_4-2)") (class "Default")
      (node (ref "D1_4") (pin "ANODE") (pinfunction "ANODE_ANODE") (pintype "passive"))
      (node (ref "L1_4") (pin "P$2") (pinfunction "2_P$2") (pintype "passive"))
      (node (ref "M4") (pin "D") (pinfunction "D_D") (pintype "passive"))
      (node (ref "M4") (pin "D5") (pinfunction "D_D5") (pintype "passive"))
      (node (ref "M4") (pin "D6") (pinfunction "D_D6") (pintype "passive"))
      (node (ref "M4") (pin "D7") (pinfunction "D_D7") (pintype "passive"))
      (node (ref "M4") (pin "D8") (pinfunction "D_D8") (pintype "passive"))
    )
    (net (code "31") (name "Net-(RS1_1-1)") (class "Default")
      (node (ref "M1") (pin "S1") (pinfunction "S_S1") (pintype "passive"))
      (node (ref "M1") (pin "S2") (pinfunction "S_S2") (pintype "passive"))
      (node (ref "M1") (pin "S3") (pinfunction "S_S3") (pintype "passive"))
      (node (ref "RS1_1") (pin "A") (pinfunction "1_A") (pintype "passive"))
      (node (ref "U1") (pin "P$6") (pinfunction "SENSE_P$6") (pintype "bidirectional"))
    )
    (net (code "32") (name "Net-(RS1_2-1)") (class "Default")
      (node (ref "M2") (pin "S1") (pinfunction "S_S1") (pintype "passive"))
      (node (ref "M2") (pin "S2") (pinfunction "S_S2") (pintype "passive"))
      (node (ref "M2") (pin "S3") (pinfunction "S_S3") (pintype "passive"))
      (node (ref "RS1_2") (pin "A") (pinfunction "1_A") (pintype "passive"))
      (node (ref "U2") (pin "P$6") (pinfunction "SENSE_P$6") (pintype "bidirectional"))
    )
    (net (code "33") (name "Net-(RS1_3-1)") (class "Default")
      (node (ref "M3") (pin "S1") (pinfunction "S_S1") (pintype "passive"))
      (node (ref "M3") (pin "S2") (pinfunction "S_S2") (pintype "passive"))
      (node (ref "M3") (pin "S3") (pinfunction "S_S3") (pintype "passive"))
      (node (ref "RS1_3") (pin "A") (pinfunction "1_A") (pintype "passive"))
      (node (ref "U3") (pin "P$6") (pinfunction "SENSE_P$6") (pintype "bidirectional"))
    )
    (net (code "34") (name "Net-(RS1_4-1)") (class "Default")
      (node (ref "M4") (pin "S1") (pinfunction "S_S1") (pintype "passive"))
      (node (ref "M4") (pin "S2") (pinfunction "S_S2") (pintype "passive"))
      (node (ref "M4") (pin "S3") (pinfunction "S_S3") (pintype "passive"))
      (node (ref "RS1_4") (pin "A") (pinfunction "1_A") (pintype "passive"))
      (node (ref "U4") (pin "P$6") (pinfunction "SENSE_P$6") (pintype "bidirectional"))
    )
    (net (code "35") (name "Net-(U1-FBX)") (class "Default")
      (node (ref "RFB1_1") (pin "2") (pinfunction "2_2") (pintype "passive"))
      (node (ref "RFB2_1") (pin "1") (pinfunction "1_1") (pintype "passive"))
      (node (ref "U1") (pin "P$2") (pinfunction "FBX_P$2") (pintype "bidirectional"))
    )
    (net (code "36") (name "Net-(U1-GATE)") (class "Default")
      (node (ref "M1") (pin "G") (pinfunction "G_G") (pintype "passive"))
      (node (ref "U1") (pin "P$7") (pinfunction "GATE_P$7") (pintype "bidirectional"))
    )
    (net (code "37") (name "Net-(U1-INTVCC)") (class "Default")
      (node (ref "CVCC_1") (pin "1") (pinfunction "1_1") (pintype "passive"))
      (node (ref "U1") (pin "P$8") (pinfunction "INTVCC_P$8") (pintype "bidirectional"))
    )
    (net (code "38") (name "Net-(U1-RT)") (class "Default")
      (node (ref "RT_1") (pin "2") (pinfunction "2_2") (pintype "passive"))
      (node (ref "U1") (pin "P$4") (pinfunction "RT_P$4") (pintype "bidirectional"))
    )
    (net (code "39") (name "Net-(U1-SS)") (class "Default")
      (node (ref "CSS_1") (pin "1") (pinfunction "1_1") (pintype "passive"))
      (node (ref "U1") (pin "P$3") (pinfunction "SS_P$3") (pintype "bidirectional"))
    )
    (net (code "40") (name "Net-(U1-VC)") (class "Default")
      (node (ref "CC2_1") (pin "1") (pinfunction "1_1") (pintype "passive"))
      (node (ref "RC_1") (pin "2") (pinfunction "2_2") (pintype "passive"))
      (node (ref "U1") (pin "P$1") (pinfunction "VC_P$1") (pintype "bidirectional"))
    )
    (net (code "41") (name "Net-(U2-FBX)") (class "Default")
      (node (ref "RFB1_2") (pin "2") (pinfunction "2_2") (pintype "passive"))
      (node (ref "RFB2_2") (pin "1") (pinfunction "1_1") (pintype "passive"))
      (node (ref "U2") (pin "P$2") (pinfunction "FBX_P$2") (pintype "bidirectional"))
    )
    (net (code "42") (name "Net-(U2-GATE)") (class "Default")
      (node (ref "M2") (pin "G") (pinfunction "G_G") (pintype "passive"))
      (node (ref "U2") (pin "P$7") (pinfunction "GATE_P$7") (pintype "bidirectional"))
    )
    (net (code "43") (name "Net-(U2-INTVCC)") (class "Default")
      (node (ref "CVCC_2") (pin "1") (pinfunction "1_1") (pintype "passive"))
      (node (ref "U2") (pin "P$8") (pinfunction "INTVCC_P$8") (pintype "bidirectional"))
    )
    (net (code "44") (name "Net-(U2-RT)") (class "Default")
      (node (ref "RT_2") (pin "2") (pinfunction "2_2") (pintype "passive"))
      (node (ref "U2") (pin "P$4") (pinfunction "RT_P$4") (pintype "bidirectional"))
    )
    (net (code "45") (name "Net-(U2-SS)") (class "Default")
      (node (ref "CSS_2") (pin "1") (pinfunction "1_1") (pintype "passive"))
      (node (ref "U2") (pin "P$3") (pinfunction "SS_P$3") (pintype "bidirectional"))
    )
    (net (code "46") (name "Net-(U2-VC)") (class "Default")
      (node (ref "CC2_2") (pin "1") (pinfunction "1_1") (pintype "passive"))
      (node (ref "RC_2") (pin "2") (pinfunction "2_2") (pintype "passive"))
      (node (ref "U2") (pin "P$1") (pinfunction "VC_P$1") (pintype "bidirectional"))
    )
    (net (code "47") (name "Net-(U3-FBX)") (class "Default")
      (node (ref "RFB1_3") (pin "2") (pinfunction "2_2") (pintype "passive"))
      (node (ref "RFB2_3") (pin "1") (pinfunction "1_1") (pintype "passive"))
      (node (ref "U3") (pin "P$2") (pinfunction "FBX_P$2") (pintype "bidirectional"))
    )
    (net (code "48") (name "Net-(U3-GATE)") (class "Default")
      (node (ref "M3") (pin "G") (pinfunction "G_G") (pintype "passive"))
      (node (ref "U3") (pin "P$7") (pinfunction "GATE_P$7") (pintype "bidirectional"))
    )
    (net (code "49") (name "Net-(U3-INTVCC)") (class "Default")
      (node (ref "CVCC_3") (pin "1") (pinfunction "1_1") (pintype "passive"))
      (node (ref "U3") (pin "P$8") (pinfunction "INTVCC_P$8") (pintype "bidirectional"))
    )
    (net (code "50") (name "Net-(U3-RT)") (class "Default")
      (node (ref "RT_3") (pin "2") (pinfunction "2_2") (pintype "passive"))
      (node (ref "U3") (pin "P$4") (pinfunction "RT_P$4") (pintype "bidirectional"))
    )
    (net (code "51") (name "Net-(U3-SS)") (class "Default")
      (node (ref "CSS_3") (pin "1") (pinfunction "1_1") (pintype "passive"))
      (node (ref "U3") (pin "P$3") (pinfunction "SS_P$3") (pintype "bidirectional"))
    )
    (net (code "52") (name "Net-(U3-VC)") (class "Default")
      (node (ref "CC2_3") (pin "1") (pinfunction "1_1") (pintype "passive"))
      (node (ref "RC_3") (pin "2") (pinfunction "2_2") (pintype "passive"))
      (node (ref "U3") (pin "P$1") (pinfunction "VC_P$1") (pintype "bidirectional"))
    )
    (net (code "53") (name "Net-(U4-FBX)") (class "Default")
      (node (ref "RFB1_4") (pin "2") (pinfunction "2_2") (pintype "passive"))
      (node (ref "RFB2_4") (pin "1") (pinfunction "1_1") (pintype "passive"))
      (node (ref "U4") (pin "P$2") (pinfunction "FBX_P$2") (pintype "bidirectional"))
    )
    (net (code "54") (name "Net-(U4-GATE)") (class "Default")
      (node (ref "M4") (pin "G") (pinfunction "G_G") (pintype "passive"))
      (node (ref "U4") (pin "P$7") (pinfunction "GATE_P$7") (pintype "bidirectional"))
    )
    (net (code "55") (name "Net-(U4-INTVCC)") (class "Default")
      (node (ref "CVCC_4") (pin "1") (pinfunction "1_1") (pintype "passive"))
      (node (ref "U4") (pin "P$8") (pinfunction "INTVCC_P$8") (pintype "bidirectional"))
    )
    (net (code "56") (name "Net-(U4-RT)") (class "Default")
      (node (ref "RT_4") (pin "2") (pinfunction "2_2") (pintype "passive"))
      (node (ref "U4") (pin "P$4") (pinfunction "RT_P$4") (pintype "bidirectional"))
    )
    (net (code "57") (name "Net-(U4-SS)") (class "Default")
      (node (ref "CSS_4") (pin "1") (pinfunction "1_1") (pintype "passive"))
      (node (ref "U4") (pin "P$3") (pinfunction "SS_P$3") (pintype "bidirectional"))
    )
    (net (code "58") (name "Net-(U4-VC)") (class "Default")
      (node (ref "CC2_4") (pin "1") (pinfunction "1_1") (pintype "passive"))
      (node (ref "RC_4") (pin "2") (pinfunction "2_2") (pintype "passive"))
      (node (ref "U4") (pin "P$1") (pinfunction "VC_P$1") (pintype "bidirectional"))
    )
    (net (code "59") (name "PHOTODIODE_RETURN") (class "Default")
      (node (ref "CONN13F") (pin "1") (pinfunction "1_1") (pintype "bidirectional"))
      (node (ref "DRIVECONN2") (pin "14") (pinfunction "14_14") (pintype "passive"))
    )
    (net (code "60") (name "SHDN_N") (class "Default")
      (node (ref "DRIVECONN1") (pin "8") (pinfunction "8_8") (pintype "passive"))
      (node (ref "RSHDN") (pin "2") (pinfunction "2_2") (pintype "passive"))
      (node (ref "U1") (pin "P$9") (pinfunction "SHDN_N_P$9") (pintype "bidirectional"))
      (node (ref "U2") (pin "P$9") (pinfunction "SHDN_N_P$9") (pintype "bidirectional"))
      (node (ref "U3") (pin "P$9") (pinfunction "SHDN_N_P$9") (pintype "bidirectional"))
      (node (ref "U4") (pin "P$9") (pinfunction "SHDN_N_P$9") (pintype "bidirectional"))
    )
    (net (code "61") (name "VIN_BATT_1") (class "Default")
      (node (ref "CIN_1") (pin "1") (pinfunction "1_1") (pintype "passive"))
      (node (ref "CIN_2") (pin "1") (pinfunction "1_1") (pintype "passive"))
      (node (ref "L1_1") (pin "P$1") (pinfunction "1_P$1") (pintype "passive"))
      (node (ref "L1_2") (pin "P$1") (pinfunction "1_P$1") (pintype "passive"))
      (node (ref "U1") (pin "P$10") (pinfunction "VIN_P$10") (pintype "bidirectional"))
      (node (ref "U2") (pin "P$10") (pinfunction "VIN_P$10") (pintype "bidirectional"))
      (node (ref "V6") (pin "P$1") (pinfunction "P$1_P$1") (pintype "bidirectional"))
      (node (ref "V7") (pin "P$1") (pinfunction "P$1_P$1") (pintype "bidirectional"))
    )
    (net (code "62") (name "VIN_BATT_3") (class "Default")
      (node (ref "ANTDEP2F") (pin "10") (pinfunction "10_10") (pintype "bidirectional"))
      (node (ref "ANTDEP2F") (pin "6") (pinfunction "6_6") (pintype "bidirectional"))
      (node (ref "ANTDEP2F") (pin "7") (pinfunction "7_7") (pintype "bidirectional"))
      (node (ref "ANTDEP2F") (pin "8") (pinfunction "8_8") (pintype "bidirectional"))
      (node (ref "ANTDEP2F") (pin "9") (pinfunction "9_9") (pintype "bidirectional"))
      (node (ref "ANTDEP3F") (pin "10") (pinfunction "10_10") (pintype "bidirectional"))
      (node (ref "ANTDEP3F") (pin "6") (pinfunction "6_6") (pintype "bidirectional"))
      (node (ref "ANTDEP3F") (pin "7") (pinfunction "7_7") (pintype "bidirectional"))
      (node (ref "ANTDEP3F") (pin "8") (pinfunction "8_8") (pintype "bidirectional"))
      (node (ref "ANTDEP3F") (pin "9") (pinfunction "9_9") (pintype "bidirectional"))
      (node (ref "CIN_3") (pin "1") (pinfunction "1_1") (pintype "passive"))
      (node (ref "CIN_4") (pin "1") (pinfunction "1_1") (pintype "passive"))
      (node (ref "L1_3") (pin "P$1") (pinfunction "1_P$1") (pintype "passive"))
      (node (ref "L1_4") (pin "P$1") (pinfunction "1_P$1") (pintype "passive"))
      (node (ref "U3") (pin "P$10") (pinfunction "VIN_P$10") (pintype "bidirectional"))
      (node (ref "U4") (pin "P$10") (pinfunction "VIN_P$10") (pintype "bidirectional"))
      (node (ref "V2") (pin "P$1") (pinfunction "P$1_P$1") (pintype "bidirectional"))
      (node (ref "V3") (pin "P$1") (pinfunction "P$1_P$1") (pintype "bidirectional"))
    )
    (net (code "63") (name "VIN_LION") (class "Default")
      (node (ref "ANTDEP1F") (pin "10") (pinfunction "10_10") (pintype "bidirectional"))
      (node (ref "ANTDEP1F") (pin "6") (pinfunction "6_6") (pintype "bidirectional"))
      (node (ref "ANTDEP1F") (pin "7") (pinfunction "7_7") (pintype "bidirectional"))
      (node (ref "ANTDEP1F") (pin "8") (pinfunction "8_8") (pintype "bidirectional"))
      (node (ref "ANTDEP1F") (pin "9") (pinfunction "9_9") (pintype "bidirectional"))
      (node (ref "V4") (pin "P$1") (pinfunction "P$1_P$1") (pintype "bidirectional"))
    )
    (net (code "64") (name "VOUT_1") (class "Default")
      (node (ref "COUT1_1") (pin "1") (pinfunction "1_1") (pintype "passive"))
      (node (ref "COUT2_1") (pin "1") (pinfunction "1_1") (pintype "passive"))
      (node (ref "D1_1") (pin "CATHODE") (pinfunction "CATHODE_CATHODE") (pintype "passive"))
      (node (ref "RFB2_1") (pin "2") (pinfunction "2_2") (pintype "passive"))
      (node (ref "VOUT_1") (pin "1") (pinfunction "1_1") (pintype "bidirectional"))
      (node (ref "VOUT_1") (pin "10") (pinfunction "10_10") (pintype "bidirectional"))
      (node (ref "VOUT_1") (pin "2") (pinfunction "2_2") (pintype "bidirectional"))
      (node (ref "VOUT_1") (pin "3") (pinfunction "3_3") (pintype "bidirectional"))
      (node (ref "VOUT_1") (pin "4") (pinfunction "4_4") (pintype "bidirectional"))
      (node (ref "VOUT_1") (pin "5") (pinfunction "5_5") (pintype "bidirectional"))
      (node (ref "VOUT_1") (pin "6") (pinfunction "6_6") (pintype "bidirectional"))
      (node (ref "VOUT_1") (pin "7") (pinfunction "7_7") (pintype "bidirectional"))
      (node (ref "VOUT_1") (pin "8") (pinfunction "8_8") (pintype "bidirectional"))
      (node (ref "VOUT_1") (pin "9") (pinfunction "9_9") (pintype "bidirectional"))
    )
    (net (code "65") (name "VOUT_2") (class "Default")
      (node (ref "COUT1_2") (pin "1") (pinfunction "1_1") (pintype "passive"))
      (node (ref "COUT2_2") (pin "1") (pinfunction "1_1") (pintype "passive"))
      (node (ref "D1_2") (pin "CATHODE") (pinfunction "CATHODE_CATHODE") (pintype "passive"))
      (node (ref "RFB2_2") (pin "2") (pinfunction "2_2") (pintype "passive"))
      (node (ref "VOUT_2") (pin "1") (pinfunction "1_1") (pintype "bidirectional"))
      (node (ref "VOUT_2") (pin "10") (pinfunction "10_10") (pintype "bidirectional"))
      (node (ref "VOUT_2") (pin "2") (pinfunction "2_2") (pintype "bidirectional"))
      (node (ref "VOUT_2") (pin "3") (pinfunction "3_3") (pintype "bidirectional"))
      (node (ref "VOUT_2") (pin "4") (pinfunction "4_4") (pintype "bidirectional"))
      (node (ref "VOUT_2") (pin "5") (pinfunction "5_5") (pintype "bidirectional"))
      (node (ref "VOUT_2") (pin "6") (pinfunction "6_6") (pintype "bidirectional"))
      (node (ref "VOUT_2") (pin "7") (pinfunction "7_7") (pintype "bidirectional"))
      (node (ref "VOUT_2") (pin "8") (pinfunction "8_8") (pintype "bidirectional"))
      (node (ref "VOUT_2") (pin "9") (pinfunction "9_9") (pintype "bidirectional"))
    )
    (net (code "66") (name "VOUT_3") (class "Default")
      (node (ref "COUT1_3") (pin "1") (pinfunction "1_1") (pintype "passive"))
      (node (ref "COUT2_3") (pin "1") (pinfunction "1_1") (pintype "passive"))
      (node (ref "D1_3") (pin "CATHODE") (pinfunction "CATHODE_CATHODE") (pintype "passive"))
      (node (ref "RFB2_3") (pin "2") (pinfunction "2_2") (pintype "passive"))
      (node (ref "VOUT_3") (pin "1") (pinfunction "1_1") (pintype "bidirectional"))
      (node (ref "VOUT_3") (pin "10") (pinfunction "10_10") (pintype "bidirectional"))
      (node (ref "VOUT_3") (pin "2") (pinfunction "2_2") (pintype "bidirectional"))
      (node (ref "VOUT_3") (pin "3") (pinfunction "3_3") (pintype "bidirectional"))
      (node (ref "VOUT_3") (pin "4") (pinfunction "4_4") (pintype "bidirectional"))
      (node (ref "VOUT_3") (pin "5") (pinfunction "5_5") (pintype "bidirectional"))
      (node (ref "VOUT_3") (pin "6") (pinfunction "6_6") (pintype "bidirectional"))
      (node (ref "VOUT_3") (pin "7") (pinfunction "7_7") (pintype "bidirectional"))
      (node (ref "VOUT_3") (pin "8") (pinfunction "8_8") (pintype "bidirectional"))
      (node (ref "VOUT_3") (pin "9") (pinfunction "9_9") (pintype "bidirectional"))
    )
    (net (code "67") (name "VOUT_4") (class "Default")
      (node (ref "COUT1_4") (pin "1") (pinfunction "1_1") (pintype "passive"))
      (node (ref "COUT2_4") (pin "1") (pinfunction "1_1") (pintype "passive"))
      (node (ref "D1_4") (pin "CATHODE") (pinfunction "CATHODE_CATHODE") (pintype "passive"))
      (node (ref "RFB2_4") (pin "2") (pinfunction "2_2") (pintype "passive"))
      (node (ref "VOUT_4") (pin "1") (pinfunction "1_1") (pintype "bidirectional"))
      (node (ref "VOUT_4") (pin "10") (pinfunction "10_10") (pintype "bidirectional"))
      (node (ref "VOUT_4") (pin "2") (pinfunction "2_2") (pintype "bidirectional"))
      (node (ref "VOUT_4") (pin "3") (pinfunction "3_3") (pintype "bidirectional"))
      (node (ref "VOUT_4") (pin "4") (pinfunction "4_4") (pintype "bidirectional"))
      (node (ref "VOUT_4") (pin "5") (pinfunction "5_5") (pintype "bidirectional"))
      (node (ref "VOUT_4") (pin "6") (pinfunction "6_6") (pintype "bidirectional"))
      (node (ref "VOUT_4") (pin "7") (pinfunction "7_7") (pintype "bidirectional"))
      (node (ref "VOUT_4") (pin "8") (pinfunction "8_8") (pintype "bidirectional"))
      (node (ref "VOUT_4") (pin "9") (pinfunction "9_9") (pintype "bidirectional"))
    )
    (net (code "68") (name "unconnected-(CONN13F-Pad7)") (class "Default")
      (node (ref "CONN13F") (pin "7") (pinfunction "7_7") (pintype "bidirectional"))
    )
    (net (code "69") (name "unconnected-(CONN13F-Pad8)") (class "Default")
      (node (ref "CONN13F") (pin "8") (pinfunction "8_8") (pintype "bidirectional"))
    )
    (net (code "70") (name "unconnected-(CONN13F-Pad9)") (class "Default")
      (node (ref "CONN13F") (pin "9") (pinfunction "9_9") (pintype "bidirectional"))
    )
    (net (code "71") (name "unconnected-(DRIVECONN1-Pad5)") (class "Default")
      (node (ref "DRIVECONN1") (pin "5") (pinfunction "5_5") (pintype "passive"))
    )
    (net (code "72") (name "unconnected-(DRIVECONN1-Pad10)") (class "Default")
      (node (ref "DRIVECONN1") (pin "10") (pinfunction "10_10") (pintype "passive"))
    )
    (net (code "73") (name "unconnected-(DRIVECONN2-Pad1)") (class "Default")
      (node (ref "DRIVECONN2") (pin "1") (pinfunction "1_1") (pintype "passive"))
    )
    (net (code "74") (name "unconnected-(DRIVECONN2-Pad2)") (class "Default")
      (node (ref "DRIVECONN2") (pin "2") (pinfunction "2_2") (pintype "passive"))
    )
    (net (code "75") (name "unconnected-(DRIVECONN2-Pad3)") (class "Default")
      (node (ref "DRIVECONN2") (pin "3") (pinfunction "3_3") (pintype "passive"))
    )
    (net (code "76") (name "unconnected-(DRIVECONN2-Pad5)") (class "Default")
      (node (ref "DRIVECONN2") (pin "5") (pinfunction "5_5") (pintype "passive"))
    )
    (net (code "77") (name "unconnected-(DRIVECONN2-Pad6)") (class "Default")
      (node (ref "DRIVECONN2") (pin "6") (pinfunction "6_6") (pintype "passive"))
    )
    (net (code "78") (name "unconnected-(DRIVECONN2-Pad7)") (class "Default")
      (node (ref "DRIVECONN2") (pin "7") (pinfunction "7_7") (pintype "passive"))
    )
    (net (code "79") (name "unconnected-(DRIVECONN2-Pad8)") (class "Default")
      (node (ref "DRIVECONN2") (pin "8") (pinfunction "8_8") (pintype "passive"))
    )
    (net (code "80") (name "unconnected-(DRIVECONN2-Pad9)") (class "Default")
      (node (ref "DRIVECONN2") (pin "9") (pinfunction "9_9") (pintype "passive"))
    )
  )
)
